# eCog101_I2C_TFT__96.net
KiCad netlist of a schematic drawn in EAGLE
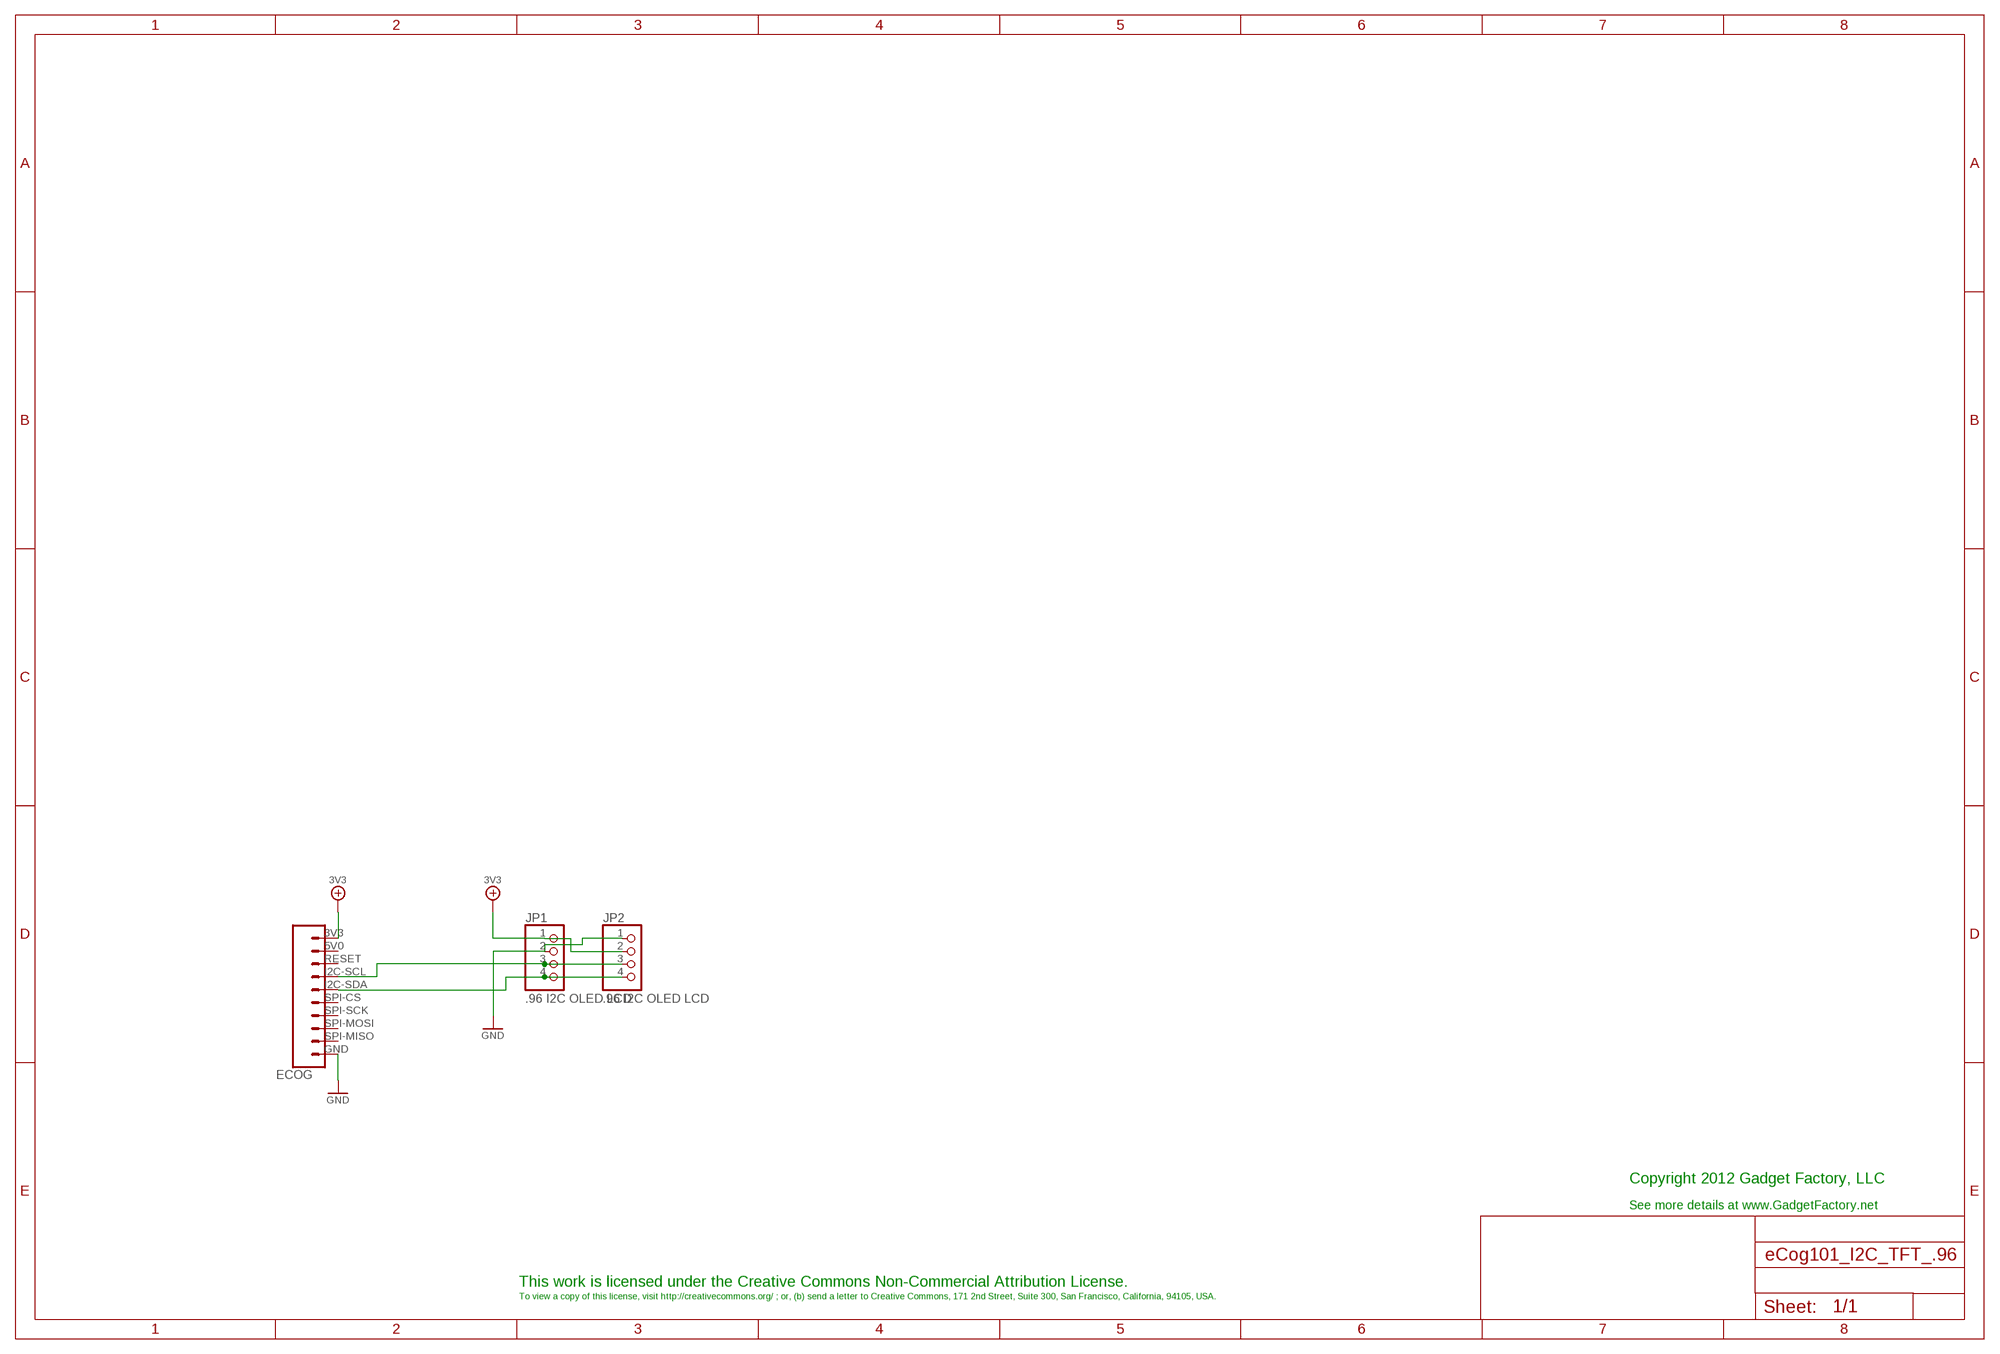
[diagram p0: schematic, sheet 1]

(export (version "E")
  (design (tool "Eeschema 10.0.6"))
  (components
    (comp (ref "ECOG")
      (value "ECOG_BUSES_ROWTHROUGHHOLE")
      (footprint "eagle-import:ECOG_BUSES_TH")
      (libsource (lib "eagle-import") (part "ECOG_BUSES_ROWTHROUGHHOLE"))
    )
    (comp (ref "JP1")
      (value ".96 I2C OLED LCD")
      (footprint "eagle-import:1X04")
      (libsource (lib "eagle-import") (part "PINHD-1X4"))
    )
    (comp (ref "JP2")
      (value ".96 I2C OLED LCD")
      (footprint "eagle-import:1X04")
      (libsource (lib "eagle-import") (part "PINHD-1X4"))
    )
  )
  (nets
    (net (code "1") (name "3V3") (class "Default")
      (node (ref "ECOG") (pin "3V3") (pinfunction "3V3_3V3") (pintype "passive"))
      (node (ref "JP1") (pin "1") (pinfunction "1_1") (pintype "passive"))
      (node (ref "JP2") (pin "2") (pinfunction "2_2") (pintype "passive"))
    )
    (net (code "2") (name "GND") (class "Default")
      (node (ref "ECOG") (pin "GND") (pinfunction "GND_GND") (pintype "passive"))
      (node (ref "JP1") (pin "2") (pinfunction "2_2") (pintype "passive"))
      (node (ref "JP2") (pin "1") (pinfunction "1_1") (pintype "passive"))
    )
    (net (code "3") (name "Net-(ECOG-PadI2C-SCL)") (class "Default")
      (node (ref "ECOG") (pin "I2C-SCL") (pinfunction "I2C-SCL_I2C-SCL") (pintype "passive"))
      (node (ref "JP1") (pin "3") (pinfunction "3_3") (pintype "passive"))
      (node (ref "JP2") (pin "3") (pinfunction "3_3") (pintype "passive"))
    )
    (net (code "4") (name "Net-(ECOG-PadI2C-SDA)") (class "Default")
      (node (ref "ECOG") (pin "I2C-SDA") (pinfunction "I2C-SDA_I2C-SDA") (pintype "passive"))
      (node (ref "JP1") (pin "4") (pinfunction "4_4") (pintype "passive"))
      (node (ref "JP2") (pin "4") (pinfunction "4_4") (pintype "passive"))
    )
    (net (code "5") (name "unconnected-(ECOG-PadSPI-CS)") (class "Default")
      (node (ref "ECOG") (pin "SPI-CS") (pinfunction "SPI-CS_SPI-CS") (pintype "passive"))
    )
    (net (code "6") (name "unconnected-(ECOG-PadSPI-MISO)") (class "Default")
      (node (ref "ECOG") (pin "SPI-MISO") (pinfunction "SPI-MISO_SPI-MISO") (pintype "passive"))
    )
    (net (code "7") (name "unconnected-(ECOG-PadSPI-MOSI)") (class "Default")
      (node (ref "ECOG") (pin "SPI-MOSI") (pinfunction "SPI-MOSI_SPI-MOSI") (pintype "passive"))
    )
    (net (code "8") (name "unconnected-(ECOG-PadSPI-SCK)") (class "Default")
      (node (ref "ECOG") (pin "SPI-SCK") (pinfunction "SPI-SCK_SPI-SCK") (pintype "passive"))
    )
    (net (code "9") (name "unconnected-(ECOG-RSV-Pad5V0)") (class "Default")
      (node (ref "ECOG") (pin "5V0") (pinfunction "RSV_5V0") (pintype "passive"))
    )
    (net (code "10") (name "unconnected-(ECOG-RSV-PadRESET)") (class "Default")
      (node (ref "ECOG") (pin "RESET") (pinfunction "RSV_RESET") (pintype "passive"))
    )
  )
)
